# BEP31_RPM_BAR.net
KiCad netlist of a schematic drawn in EAGLE
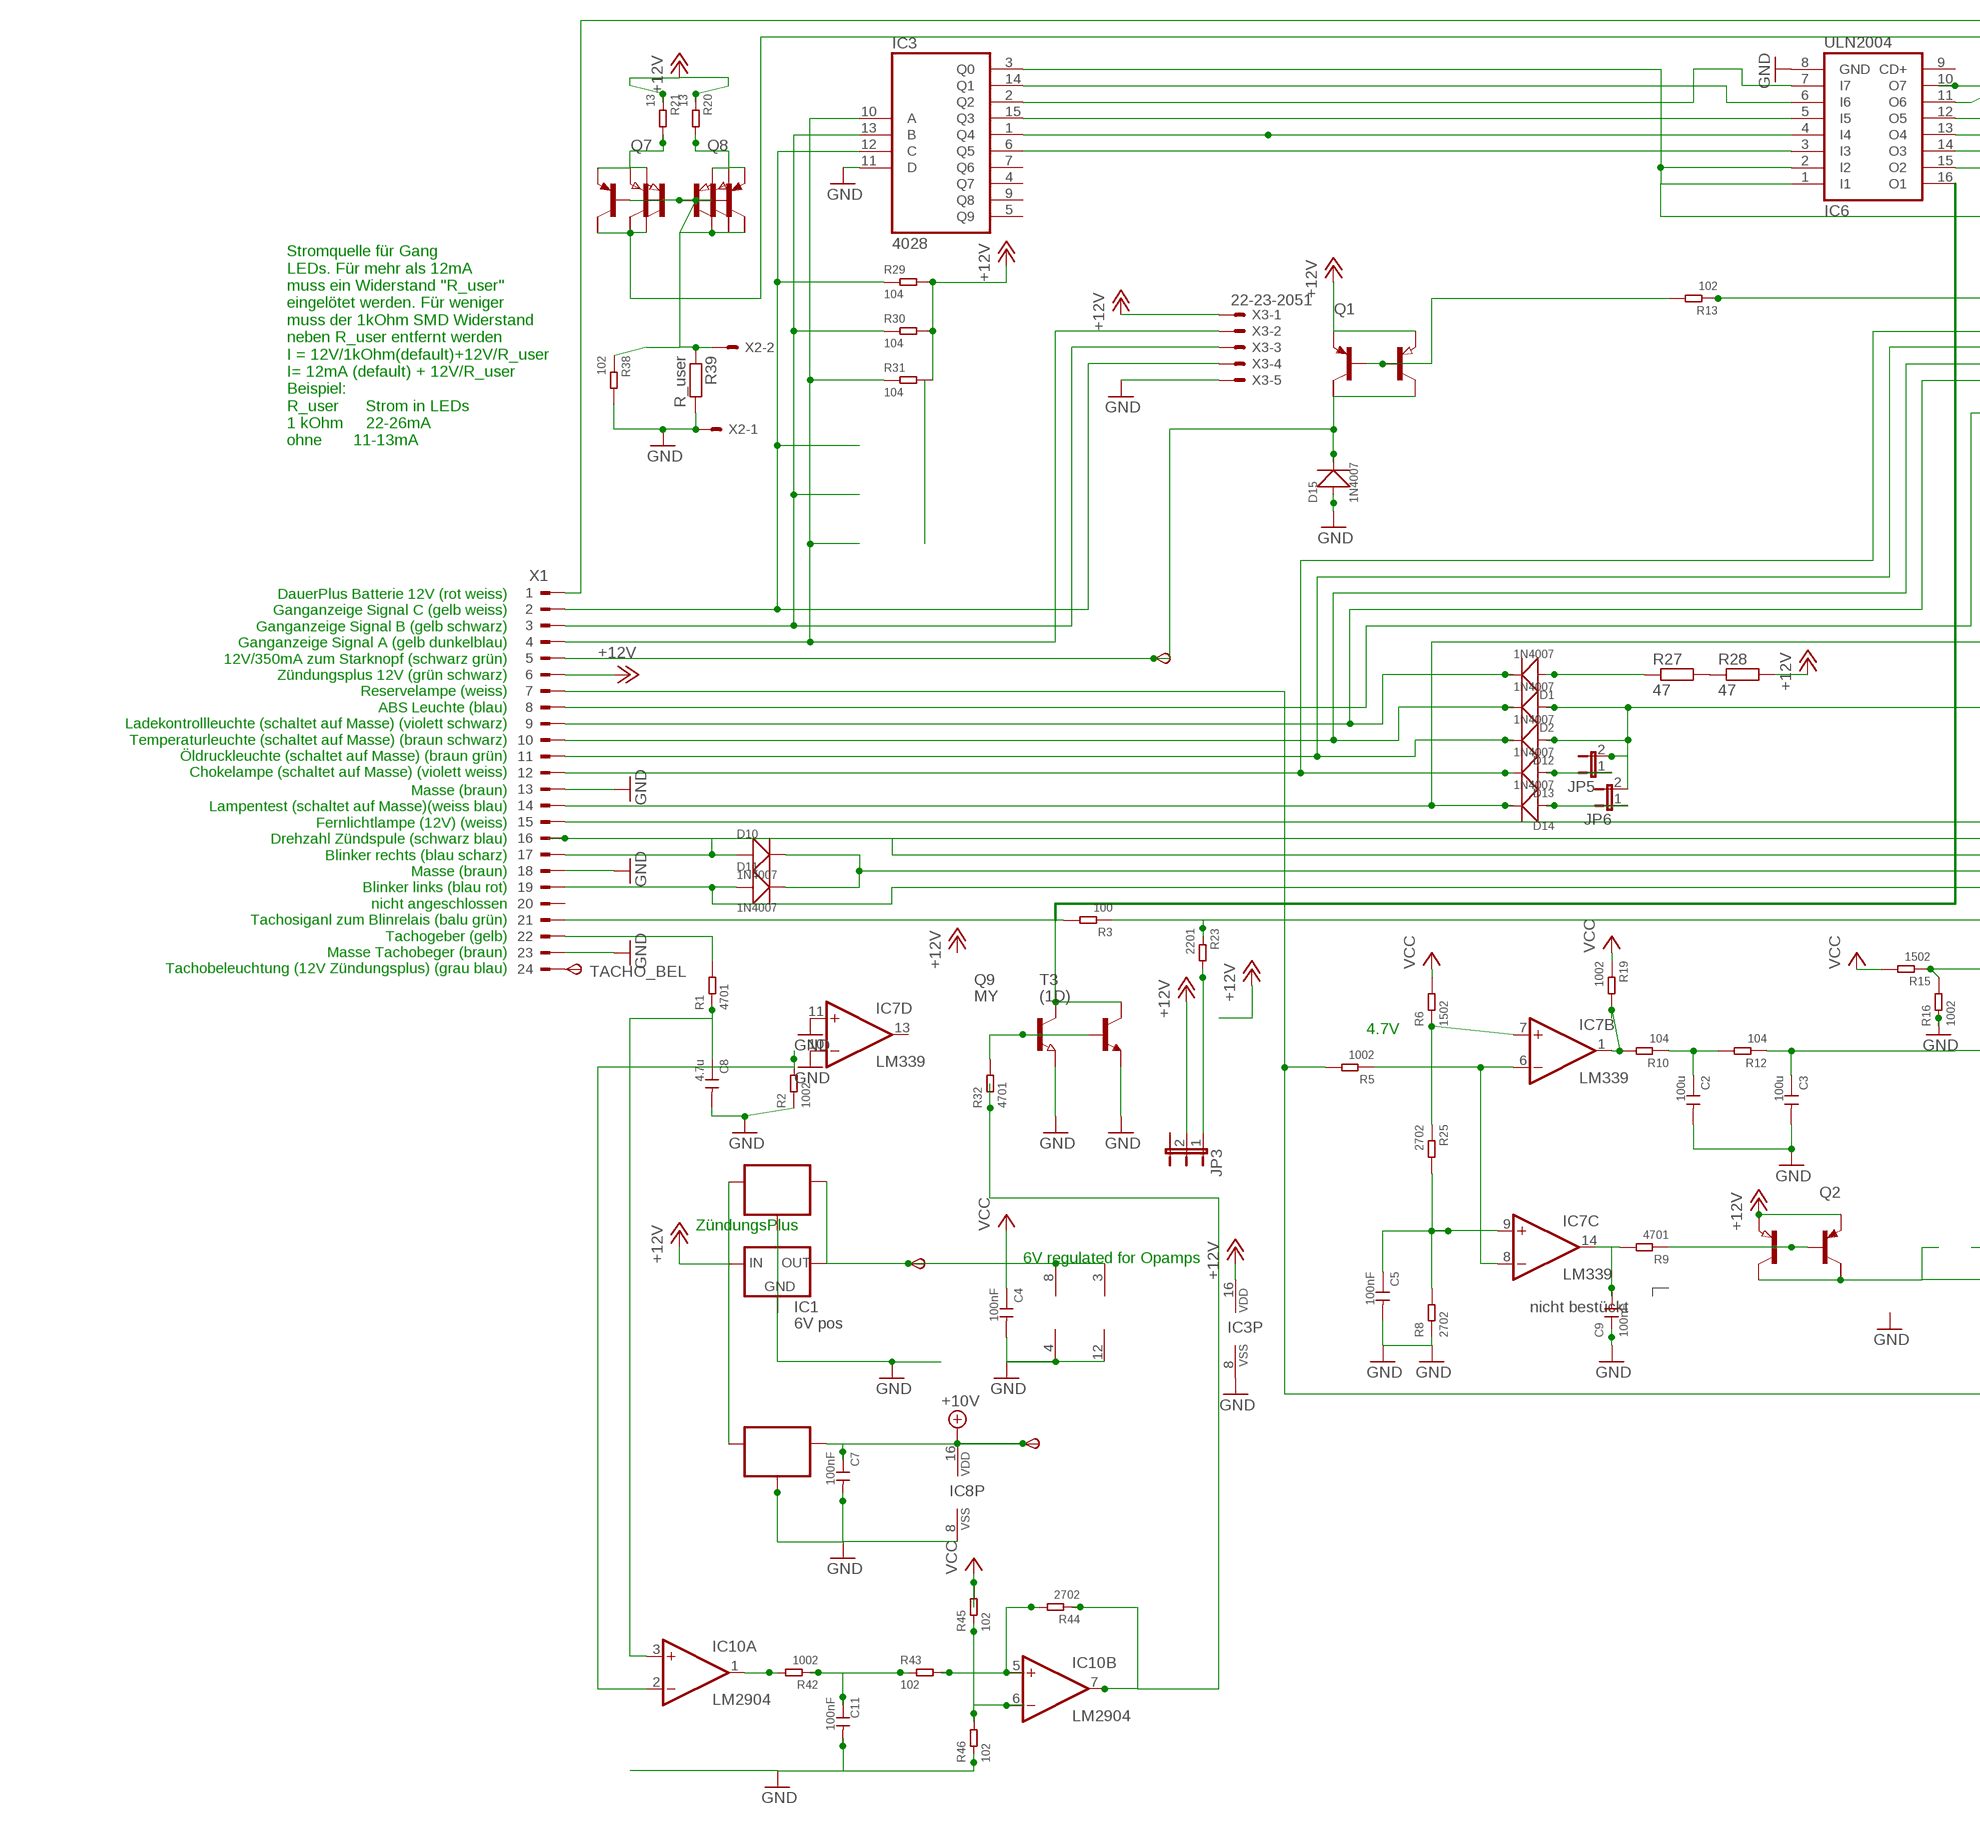
[diagram p0: schematic, sheet 1, part 1 of 2]
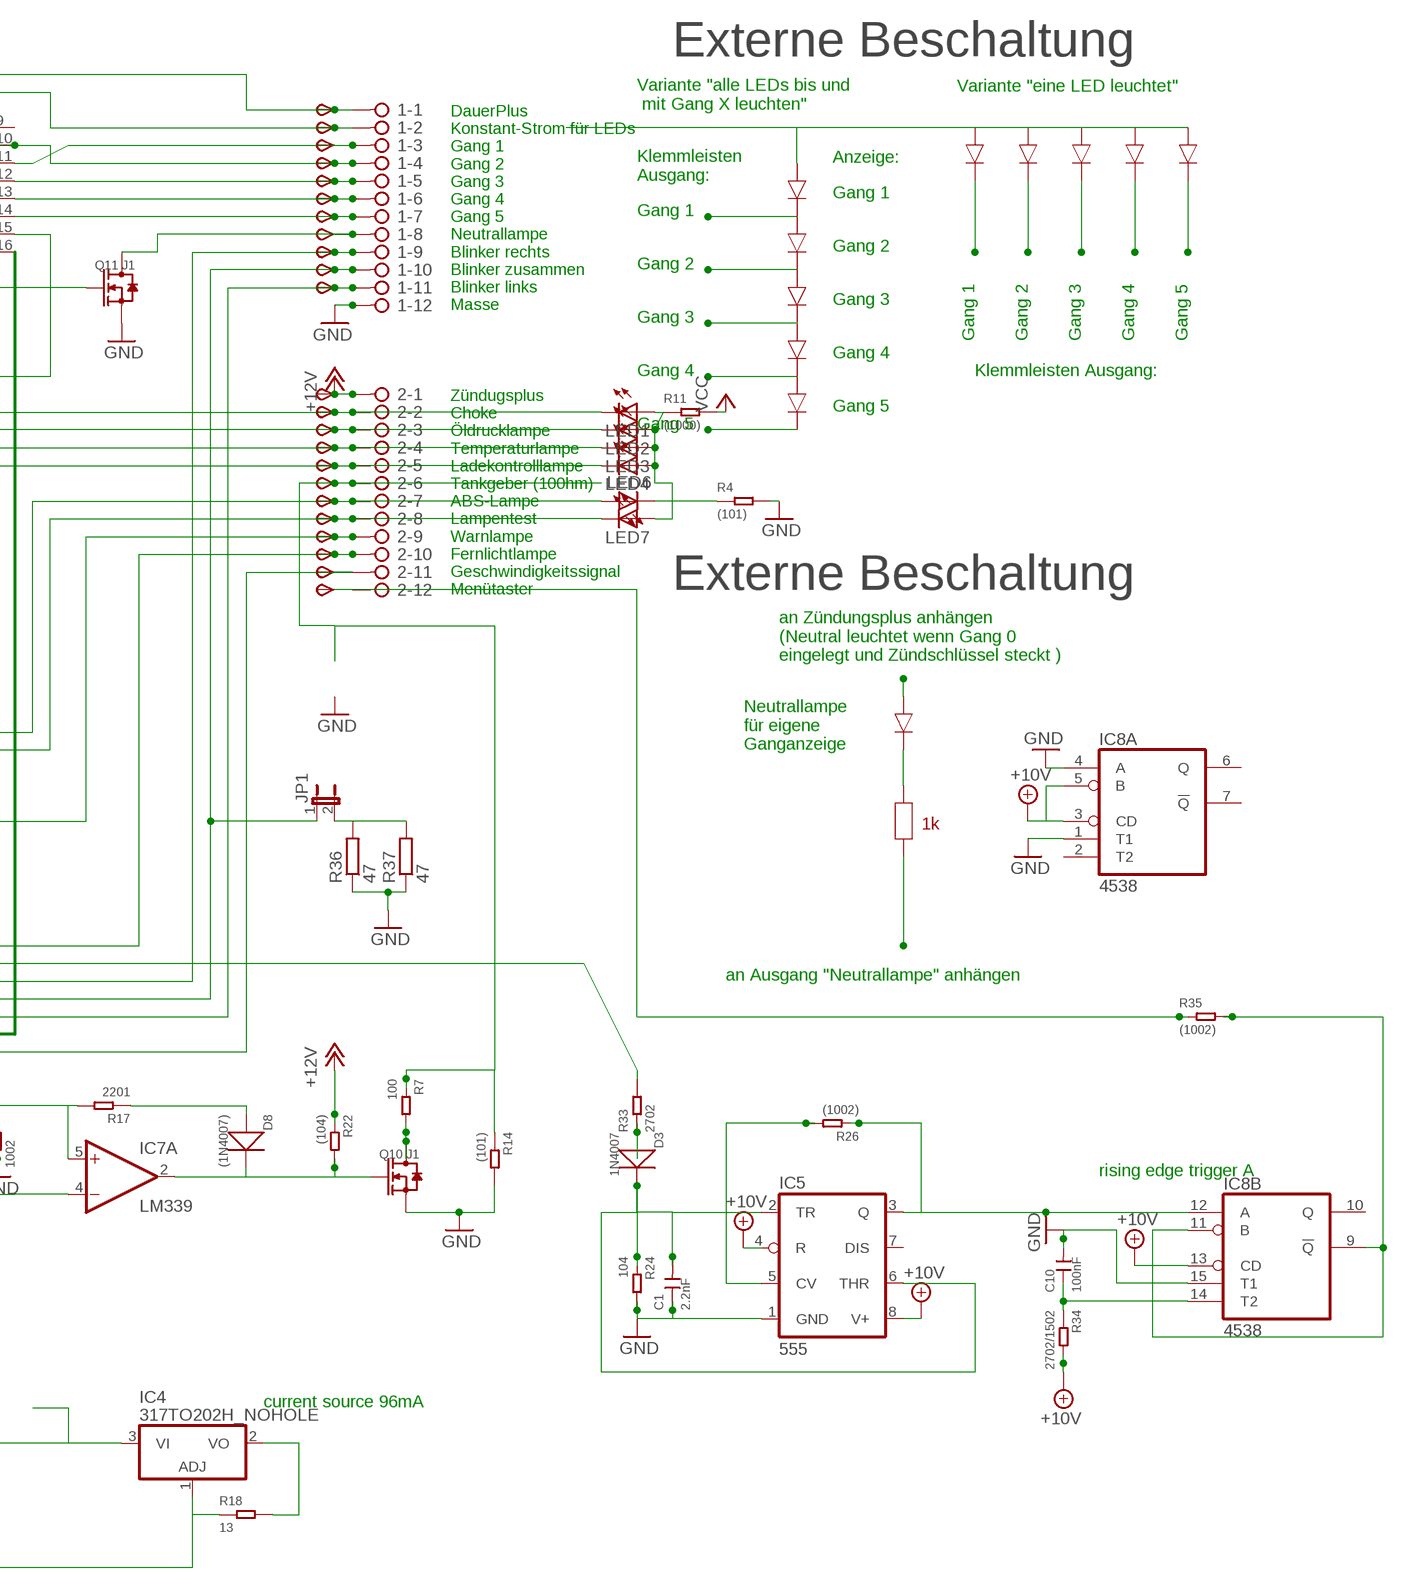
[diagram p1: schematic, sheet 1, part 2 of 2]

(export (version "E")
  (design (tool "Eeschema 10.0.6"))
  (components
    (comp (ref "1")
      (value "2081-1132")
      (footprint "eagle-import:12-PIN")
      (libsource (lib "eagle-import") (part "2081-1132"))
    )
    (comp (ref "2")
      (value "2081-1132")
      (footprint "eagle-import:12-PIN")
      (libsource (lib "eagle-import") (part "2081-1132"))
    )
    (comp (ref "6V")
      (value "TPSB1.8")
      (footprint "eagle-import:B1.8")
      (libsource (lib "eagle-import") (part "TPSB1.8"))
    )
    (comp (ref "10V")
      (value "TPSB1.8")
      (footprint "eagle-import:B1.8")
      (libsource (lib "eagle-import") (part "TPSB1.8"))
    )
    (comp (ref "C1")
      (value "2.2nF")
      (footprint "eagle-import:C0805")
      (fields (field (name "MPN") "CC0805KRX7R9BB104"))
      (libsource (lib "eagle-import") (part "CERAMIC-100NF-50V-10%-X7R(0805)"))
    )
    (comp (ref "C2")
      (value "100u")
      (footprint "eagle-import:C1206")
      (fields (field (name "MPN") "GRM31CR60J107ME39L"))
      (libsource (lib "eagle-import") (part "CERAMIC-100UF-6.3V-20%-X5R(1206)"))
    )
    (comp (ref "C3")
      (value "100u")
      (footprint "eagle-import:C1206")
      (fields (field (name "MPN") "GRM31CR60J107ME39L"))
      (libsource (lib "eagle-import") (part "CERAMIC-100UF-6.3V-20%-X5R(1206)"))
    )
    (comp (ref "C4")
      (value "100nF")
      (footprint "eagle-import:C0805")
      (fields (field (name "MPN") "CC0805KRX7R9BB104"))
      (libsource (lib "eagle-import") (part "CERAMIC-100NF-50V-10%-X7R(0805)"))
    )
    (comp (ref "C5")
      (value "100nF")
      (footprint "eagle-import:C0805")
      (fields (field (name "MPN") "CC0805KRX7R9BB104"))
      (libsource (lib "eagle-import") (part "CERAMIC-100NF-50V-10%-X7R(0805)"))
    )
    (comp (ref "C7")
      (value "100nF")
      (footprint "eagle-import:C0805")
      (fields (field (name "MPN") "CC0805KRX7R9BB104"))
      (libsource (lib "eagle-import") (part "CERAMIC-100NF-50V-10%-X7R(0805)"))
    )
    (comp (ref "C8")
      (value "4.7u")
      (footprint "eagle-import:C0805")
      (fields (field (name "MPN") "CC0805KKX5R8BB475"))
      (libsource (lib "eagle-import") (part "CERAMIC-4.7UF-25V-10%-X5R(0805)"))
    )
    (comp (ref "C9")
      (value "100nF")
      (footprint "eagle-import:C0805")
      (fields (field (name "MPN") "CC0805KRX7R9BB104"))
      (libsource (lib "eagle-import") (part "CERAMIC-100NF-50V-10%-X7R(0805)"))
    )
    (comp (ref "C10")
      (value "100nF")
      (footprint "eagle-import:C0805")
      (fields (field (name "MPN") "CC0805KRX7R9BB104"))
      (libsource (lib "eagle-import") (part "CERAMIC-100NF-50V-10%-X7R(0805)"))
    )
    (comp (ref "C11")
      (value "100nF")
      (footprint "eagle-import:C0805")
      (fields (field (name "MPN") "CC0805KRX7R9BB104"))
      (libsource (lib "eagle-import") (part "CERAMIC-100NF-50V-10%-X7R(0805)"))
    )
    (comp (ref "D1")
      (value "1N4007")
      (footprint "eagle-import:DO-214AC")
      (libsource (lib "eagle-import") (part "DIODE-GEN-PURPOSE-1KV-1A(DO-214AC)"))
    )
    (comp (ref "D2")
      (value "1N4007")
      (footprint "eagle-import:DO-214AC-1206MOUNT")
      (libsource (lib "eagle-import") (part "DIODE-GEN-PURPOSE-1KV-1A(DO-214AC)DO-214AC/1206"))
    )
    (comp (ref "D3")
      (value "1N4007")
      (footprint "eagle-import:DO-214AC")
      (libsource (lib "eagle-import") (part "DIODE-GEN-PURPOSE-1KV-1A(DO-214AC)"))
    )
    (comp (ref "D8")
      (value "(1N4007)")
      (footprint "eagle-import:DO-214AC-1206MOUNT")
      (libsource (lib "eagle-import") (part "DIODE-GEN-PURPOSE-1KV-1A(DO-214AC)DO-214AC/1206"))
    )
    (comp (ref "D10")
      (value "1N4007")
      (footprint "eagle-import:DO-214AC")
      (libsource (lib "eagle-import") (part "DIODE-GEN-PURPOSE-1KV-1A(DO-214AC)"))
    )
    (comp (ref "D11")
      (value "1N4007")
      (footprint "eagle-import:DO-214AC")
      (libsource (lib "eagle-import") (part "DIODE-GEN-PURPOSE-1KV-1A(DO-214AC)"))
    )
    (comp (ref "D12")
      (value "1N4007")
      (footprint "eagle-import:DO-214AC-1206MOUNT")
      (libsource (lib "eagle-import") (part "DIODE-GEN-PURPOSE-1KV-1A(DO-214AC)DO-214AC/1206"))
    )
    (comp (ref "D13")
      (value "1N4007")
      (footprint "eagle-import:DO-214AC-1206MOUNT")
      (libsource (lib "eagle-import") (part "DIODE-GEN-PURPOSE-1KV-1A(DO-214AC)DO-214AC/1206"))
    )
    (comp (ref "D14")
      (value "1N4007")
      (footprint "eagle-import:DO-214AC-1206MOUNT")
      (libsource (lib "eagle-import") (part "DIODE-GEN-PURPOSE-1KV-1A(DO-214AC)DO-214AC/1206"))
    )
    (comp (ref "D15")
      (value "1N4007")
      (footprint "eagle-import:DO-214AC")
      (libsource (lib "eagle-import") (part "DIODE-GEN-PURPOSE-1KV-1A(DO-214AC)"))
    )
    (comp (ref "IC1")
      (value "6V pos")
      (footprint "eagle-import:78LXX")
      (libsource (lib "eagle-import") (part "v-reg_78LXX"))
    )
    (comp (ref "IC2")
      (value "78LXXSOT89_ROUND")
      (footprint "eagle-import:SOT89_ROUND")
      (libsource (lib "eagle-import") (part "78LXXSOT89_ROUND"))
    )
    (comp (ref "IC3")
      (value "4028")
      (footprint "eagle-import:SO16")
      (libsource (lib "eagle-import") (part "4028D"))
    )
    (comp (ref "IC4")
      (value "317TO202H_NOHOLE")
      (footprint "eagle-import:TO220H_NOHOLE")
      (libsource (lib "eagle-import") (part "317TO202H_NOHOLE"))
    )
    (comp (ref "IC5")
      (value "555")
      (footprint "eagle-import:SO08")
      (libsource (lib "eagle-import") (part "555DNE"))
    )
    (comp (ref "IC6")
      (value "ULN2004")
      (footprint "eagle-import:SO16")
      (libsource (lib "eagle-import") (part "ULN2004AD"))
    )
    (comp (ref "IC7")
      (value "LM339")
      (footprint "eagle-import:SO14")
      (libsource (lib "eagle-import") (part "LM339D"))
    )
    (comp (ref "IC8")
      (value "4538")
      (footprint "eagle-import:SO16")
      (libsource (lib "eagle-import") (part "4538D"))
    )
    (comp (ref "IC9")
      (value "78LXXSOT89_ROUND")
      (footprint "eagle-import:SOT89_ROUND")
      (libsource (lib "eagle-import") (part "78LXXSOT89_ROUND"))
    )
    (comp (ref "IC10")
      (value "LM2904")
      (footprint "eagle-import:SO08")
      (libsource (lib "eagle-import") (part "LM358D"))
    )
    (comp (ref "JP1")
      (value "JP1E")
      (footprint "eagle-import:JP1")
      (libsource (lib "eagle-import") (part "JP1E"))
    )
    (comp (ref "JP3")
      (value "JP2E")
      (footprint "eagle-import:JP2")
      (libsource (lib "eagle-import") (part "JP2E"))
    )
    (comp (ref "JP5")
      (value "JP1E")
      (footprint "eagle-import:JP1")
      (libsource (lib "eagle-import") (part "JP1E"))
    )
    (comp (ref "JP6")
      (value "JP1E")
      (footprint "eagle-import:JP1")
      (libsource (lib "eagle-import") (part "JP1E"))
    )
    (comp (ref "LED1")
      (value "LEDLD260")
      (footprint "eagle-import:LD260")
      (libsource (lib "eagle-import") (part "LEDLD260"))
    )
    (comp (ref "LED2")
      (value "LEDLD260")
      (footprint "eagle-import:LD260")
      (libsource (lib "eagle-import") (part "LEDLD260"))
    )
    (comp (ref "LED3")
      (value "LEDLD260")
      (footprint "eagle-import:LD260")
      (libsource (lib "eagle-import") (part "LEDLD260"))
    )
    (comp (ref "LED4")
      (value "LEDLD260")
      (footprint "eagle-import:LD260")
      (libsource (lib "eagle-import") (part "LEDLD260"))
    )
    (comp (ref "LED6")
      (value "LEDLD260")
      (footprint "eagle-import:LD260")
      (libsource (lib "eagle-import") (part "LEDLD260"))
    )
    (comp (ref "LED7")
      (value "LEDLD260")
      (footprint "eagle-import:LD260")
      (libsource (lib "eagle-import") (part "LEDLD260"))
    )
    (comp (ref "Q1")
      (value "PNP-TRANSISTOR_SOT89")
      (footprint "eagle-import:SOT89")
      (libsource (lib "eagle-import") (part "PNP-TRANSISTOR_SOT89"))
    )
    (comp (ref "Q2")
      (value "PNP-TRANSISTOR_SOT89")
      (footprint "eagle-import:SOT89")
      (libsource (lib "eagle-import") (part "PNP-TRANSISTOR_SOT89"))
    )
    (comp (ref "Q3")
      (value "AH-16")
      (footprint "eagle-import:SOT223")
      (libsource (lib "eagle-import") (part "BCP53T1"))
    )
    (comp (ref "Q4")
      (value "(AH-16)")
      (footprint "eagle-import:SOT223")
      (libsource (lib "eagle-import") (part "BCP53T1"))
    )
    (comp (ref "Q5")
      (value "(AH-16)")
      (footprint "eagle-import:SOT223")
      (libsource (lib "eagle-import") (part "BCP53T1"))
    )
    (comp (ref "Q6")
      (value "(AH-16)")
      (footprint "eagle-import:SOT223")
      (libsource (lib "eagle-import") (part "BCP53T1"))
    )
    (comp (ref "Q7")
      (value "PNP-TRANSISTOR_SOT89")
      (footprint "eagle-import:SOT89")
      (libsource (lib "eagle-import") (part "PNP-TRANSISTOR_SOT89"))
    )
    (comp (ref "Q8")
      (value "PNP-TRANSISTOR_SOT89")
      (footprint "eagle-import:SOT89")
      (libsource (lib "eagle-import") (part "PNP-TRANSISTOR_SOT89"))
    )
    (comp (ref "Q9")
      (value "MY")
      (footprint "eagle-import:SOT89")
      (libsource (lib "eagle-import") (part "NPN-TRANSISTOR_SOT89"))
    )
    (comp (ref "Q10")
      (value "J1")
      (footprint "eagle-import:SOT-23")
      (fields (field (name "MPN") "BSS138W-7-F"))
      (libsource (lib "eagle-import") (part "SMD-MOSFET-N-CH-50V-200MA-BSS138W-7-F(SOT-23)"))
    )
    (comp (ref "Q11")
      (value "J1")
      (footprint "eagle-import:SOT-23")
      (fields (field (name "MPN") "BSS138W-7-F"))
      (libsource (lib "eagle-import") (part "SMD-MOSFET-N-CH-50V-200MA-BSS138W-7-F(SOT-23)"))
    )
    (comp (ref "R1")
      (value "4701")
      (footprint "eagle-import:R0805")
      (fields (field (name "MPN") "RC0805JR-074K7L"))
      (libsource (lib "eagle-import") (part "SMD-RES-4.7K-5%-1/8W(0805)"))
    )
    (comp (ref "R2")
      (value "1002")
      (footprint "eagle-import:R0805")
      (fields (field (name "MPN") "RC0805FR-0710KL"))
      (libsource (lib "eagle-import") (part "SMD-RES-10K-1%-1/8W(0805)"))
    )
    (comp (ref "R3")
      (value "100")
      (footprint "eagle-import:R0805")
      (fields (field (name "MPN") "RC0805JR-07220RL"))
      (libsource (lib "eagle-import") (part "SMD-RES-220R-5%-1/8W(0805)"))
    )
    (comp (ref "R4")
      (value "(101)")
      (footprint "eagle-import:R0805")
      (fields (field (name "MPN") "RC0805JR-07100RL"))
      (libsource (lib "eagle-import") (part "SMD-RES-100R-5%-1/8W(0805)"))
    )
    (comp (ref "R5")
      (value "1002")
      (footprint "eagle-import:R0805")
      (fields (field (name "MPN") "RC0805FR-0710KL"))
      (libsource (lib "eagle-import") (part "SMD-RES-10K-1%-1/8W(0805)"))
    )
    (comp (ref "R6")
      (value "1502")
      (footprint "eagle-import:R0805")
      (fields (field (name "MPN") "RC0805FR-0710KL"))
      (libsource (lib "eagle-import") (part "SMD-RES-10K-1%-1/8W(0805)"))
    )
    (comp (ref "R7")
      (value "100")
      (footprint "eagle-import:R0805")
      (fields (field (name "MPN") "RC0805JR-072K2L"))
      (libsource (lib "eagle-import") (part "SMD-RES-2.2K-5%-1/8W(0805)"))
    )
    (comp (ref "R8")
      (value "2702")
      (footprint "eagle-import:R0805")
      (fields (field (name "MPN") "RC0805JR-074K7L"))
      (libsource (lib "eagle-import") (part "SMD-RES-4.7K-5%-1/8W(0805)"))
    )
    (comp (ref "R9")
      (value "4701")
      (footprint "eagle-import:R0805")
      (fields (field (name "MPN") "RC0805JR-074K7L"))
      (libsource (lib "eagle-import") (part "SMD-RES-4.7K-5%-1/8W(0805)"))
    )
    (comp (ref "R10")
      (value "104")
      (footprint "eagle-import:R0805")
      (fields (field (name "MPN") "RC0805FR-0710KL"))
      (libsource (lib "eagle-import") (part "SMD-RES-10K-1%-1/8W(0805)"))
    )
    (comp (ref "R11")
      (value "(1000)")
      (footprint "eagle-import:R0805")
      (fields (field (name "MPN") "RC0805JR-07100RL"))
      (libsource (lib "eagle-import") (part "SMD-RES-100R-5%-1/8W(0805)"))
    )
    (comp (ref "R12")
      (value "104")
      (footprint "eagle-import:R0805")
      (fields (field (name "MPN") "RC0805FR-0710KL"))
      (libsource (lib "eagle-import") (part "SMD-RES-10K-1%-1/8W(0805)"))
    )
    (comp (ref "R13")
      (value "102")
      (footprint "eagle-import:R0805")
      (fields (field (name "MPN") "RC0805JR-071KL"))
      (libsource (lib "eagle-import") (part "SMD-RES-1K-5%-1/8W(0805)"))
    )
    (comp (ref "R14")
      (value "(101)")
      (footprint "eagle-import:R0805")
      (fields (field (name "MPN") "RC0805JR-072K2L"))
      (libsource (lib "eagle-import") (part "SMD-RES-2.2K-5%-1/8W(0805)"))
    )
    (comp (ref "R15")
      (value "1502")
      (footprint "eagle-import:R0805")
      (fields (field (name "MPN") "RC0805FR-0710KL"))
      (libsource (lib "eagle-import") (part "SMD-RES-10K-1%-1/8W(0805)"))
    )
    (comp (ref "R16")
      (value "1002")
      (footprint "eagle-import:R0805")
      (fields (field (name "MPN") "RC0805FR-0710KL"))
      (libsource (lib "eagle-import") (part "SMD-RES-10K-1%-1/8W(0805)"))
    )
    (comp (ref "R17")
      (value "2201")
      (footprint "eagle-import:R0805")
      (fields (field (name "MPN") "RC0805JR-072K2L"))
      (libsource (lib "eagle-import") (part "SMD-RES-2.2K-5%-1/8W(0805)"))
    )
    (comp (ref "R18")
      (value "13")
      (footprint "eagle-import:R1206")
      (fields (field (name "MPN") "RC1206JR-0713RL"))
      (libsource (lib "eagle-import") (part "SMD-RES-13R-5%-1/4W(1206)"))
    )
    (comp (ref "R19")
      (value "1002")
      (footprint "eagle-import:R0805")
      (fields (field (name "MPN") "RC0805FR-0710KL"))
      (libsource (lib "eagle-import") (part "SMD-RES-10K-1%-1/8W(0805)"))
    )
    (comp (ref "R20")
      (value "13")
      (footprint "eagle-import:R1206")
      (fields (field (name "MPN") "RC1206JR-0713RL"))
      (libsource (lib "eagle-import") (part "SMD-RES-13R-5%-1/4W(1206)"))
    )
    (comp (ref "R21")
      (value "13")
      (footprint "eagle-import:R1206")
      (fields (field (name "MPN") "RC1206JR-0713RL"))
      (libsource (lib "eagle-import") (part "SMD-RES-13R-5%-1/4W(1206)"))
    )
    (comp (ref "R22")
      (value "(104)")
      (footprint "eagle-import:R0805")
      (fields (field (name "MPN") "RC0805FR-0710KL"))
      (libsource (lib "eagle-import") (part "SMD-RES-10K-1%-1/8W(0805)"))
    )
    (comp (ref "R23")
      (value "2201")
      (footprint "eagle-import:R0805")
      (fields (field (name "MPN") "RC0805JR-072K2L"))
      (libsource (lib "eagle-import") (part "SMD-RES-2.2K-5%-1/8W(0805)"))
    )
    (comp (ref "R24")
      (value "104")
      (footprint "eagle-import:R0805")
      (fields (field (name "MPN") "RC0805FR-0710KL"))
      (libsource (lib "eagle-import") (part "SMD-RES-10K-1%-1/8W(0805)"))
    )
    (comp (ref "R25")
      (value "2702")
      (footprint "eagle-import:R0805")
      (fields (field (name "MPN") "RC0805JR-074K7L"))
      (libsource (lib "eagle-import") (part "SMD-RES-4.7K-5%-1/8W(0805)"))
    )
    (comp (ref "R26")
      (value "(1002)")
      (footprint "eagle-import:R0805")
      (fields (field (name "MPN") "RC0805FR-0710KL"))
      (libsource (lib "eagle-import") (part "SMD-RES-10K-1%-1/8W(0805)"))
    )
    (comp (ref "R27")
      (value "47")
      (footprint "eagle-import:V235_17_1MM")
      (libsource (lib "eagle-import") (part "R-EU_V235/17_1MM"))
    )
    (comp (ref "R28")
      (value "47")
      (footprint "eagle-import:V235_17_1MM")
      (libsource (lib "eagle-import") (part "R-EU_V235/17_1MM"))
    )
    (comp (ref "R29")
      (value "104")
      (footprint "eagle-import:R0805")
      (fields (field (name "MPN") "RC0805FR-0710KL"))
      (libsource (lib "eagle-import") (part "SMD-RES-10K-1%-1/8W(0805)"))
    )
    (comp (ref "R30")
      (value "104")
      (footprint "eagle-import:R0805")
      (fields (field (name "MPN") "RC0805FR-0710KL"))
      (libsource (lib "eagle-import") (part "SMD-RES-10K-1%-1/8W(0805)"))
    )
    (comp (ref "R31")
      (value "104")
      (footprint "eagle-import:R0805")
      (fields (field (name "MPN") "RC0805FR-0710KL"))
      (libsource (lib "eagle-import") (part "SMD-RES-10K-1%-1/8W(0805)"))
    )
    (comp (ref "R32")
      (value "4701")
      (footprint "eagle-import:R0805")
      (fields (field (name "MPN") "RC0805JR-074K7L"))
      (libsource (lib "eagle-import") (part "SMD-RES-4.7K-5%-1/8W(0805)"))
    )
    (comp (ref "R33")
      (value "2702")
      (footprint "eagle-import:R0805")
      (fields (field (name "MPN") "RC0805FR-0710KL"))
      (libsource (lib "eagle-import") (part "SMD-RES-10K-1%-1/8W(0805)"))
    )
    (comp (ref "R34")
      (value "2702/1502")
      (footprint "eagle-import:R0805")
      (fields (field (name "MPN") "RC0805JR-074K7L"))
      (libsource (lib "eagle-import") (part "SMD-RES-4.7K-5%-1/8W(0805)"))
    )
    (comp (ref "R35")
      (value "(1002)")
      (footprint "eagle-import:R0805")
      (fields (field (name "MPN") "RC0805JR-074K7L"))
      (libsource (lib "eagle-import") (part "SMD-RES-4.7K-5%-1/8W(0805)"))
    )
    (comp (ref "R36")
      (value "47")
      (footprint "eagle-import:V235_17_1MM")
      (libsource (lib "eagle-import") (part "R-EU_V235/17_1MM"))
    )
    (comp (ref "R37")
      (value "47")
      (footprint "eagle-import:V235_17_1MM")
      (libsource (lib "eagle-import") (part "R-EU_V235/17_1MM"))
    )
    (comp (ref "R38")
      (value "102")
      (footprint "eagle-import:R0805")
      (fields (field (name "MPN") "RC0805JR-071KL"))
      (libsource (lib "eagle-import") (part "SMD-RES-1K-5%-1/8W(0805)"))
    )
    (comp (ref "R39")
      (value "R_user")
      (footprint "eagle-import:R0805")
      (libsource (lib "eagle-import") (part "R-EU_R0805"))
    )
    (comp (ref "R42")
      (value "1002")
      (footprint "eagle-import:R0805")
      (fields (field (name "MPN") "RC0805FR-0710KL"))
      (libsource (lib "eagle-import") (part "SMD-RES-10K-1%-1/8W(0805)"))
    )
    (comp (ref "R43")
      (value "102")
      (footprint "eagle-import:R0805")
      (fields (field (name "MPN") "RC0805JR-071KL"))
      (libsource (lib "eagle-import") (part "SMD-RES-1K-5%-1/8W(0805)"))
    )
    (comp (ref "R44")
      (value "2702")
      (footprint "eagle-import:R0805")
      (fields (field (name "MPN") "RC0805JR-074K7L"))
      (libsource (lib "eagle-import") (part "SMD-RES-4.7K-5%-1/8W(0805)"))
    )
    (comp (ref "R45")
      (value "102")
      (footprint "eagle-import:R0805")
      (fields (field (name "MPN") "RC0805JR-071KL"))
      (libsource (lib "eagle-import") (part "SMD-RES-1K-5%-1/8W(0805)"))
    )
    (comp (ref "R46")
      (value "102")
      (footprint "eagle-import:R0805")
      (fields (field (name "MPN") "RC0805JR-071KL"))
      (libsource (lib "eagle-import") (part "SMD-RES-1K-5%-1/8W(0805)"))
    )
    (comp (ref "START")
      (value "TPSB1.8")
      (footprint "eagle-import:B1.8")
      (libsource (lib "eagle-import") (part "TPSB1.8"))
    )
    (comp (ref "T1")
      (value "PNP2SM8")
      (footprint "eagle-import:SM8")
      (libsource (lib "eagle-import") (part "PNP2SM8"))
    )
    (comp (ref "T3")
      (value "(1D)")
      (footprint "eagle-import:SOT23-BEC")
      (libsource (lib "eagle-import") (part "-NPN-SOT23-BECMMBTA42LT1"))
    )
    (comp (ref "TACHO_BEL")
      (value "TPSP1_1MM")
      (footprint "eagle-import:P1_1.0MM")
      (libsource (lib "eagle-import") (part "TPSP1_1MM"))
    )
    (comp (ref "TP1")
      (value "TPSB1.8")
      (footprint "eagle-import:B1.8")
      (libsource (lib "eagle-import") (part "TPSB1.8"))
    )
    (comp (ref "TP2")
      (value "TPSB1.8")
      (footprint "eagle-import:B1.8")
      (libsource (lib "eagle-import") (part "TPSB1.8"))
    )
    (comp (ref "TP3")
      (value "TPSB1.8")
      (footprint "eagle-import:B1.8")
      (libsource (lib "eagle-import") (part "TPSB1.8"))
    )
    (comp (ref "TP4")
      (value "TPSB1.8")
      (footprint "eagle-import:B1.8")
      (libsource (lib "eagle-import") (part "TPSB1.8"))
    )
    (comp (ref "TP5")
      (value "TPSB1.8")
      (footprint "eagle-import:B1.8")
      (libsource (lib "eagle-import") (part "TPSB1.8"))
    )
    (comp (ref "TP6")
      (value "TPSB1.8")
      (footprint "eagle-import:B1.8")
      (libsource (lib "eagle-import") (part "TPSB1.8"))
    )
    (comp (ref "TP7")
      (value "TPSB1.8")
      (footprint "eagle-import:B1.8")
      (libsource (lib "eagle-import") (part "TPSB1.8"))
    )
    (comp (ref "TP8")
      (value "TPSB1.8")
      (footprint "eagle-import:B1.8")
      (libsource (lib "eagle-import") (part "TPSB1.8"))
    )
    (comp (ref "TP9")
      (value "TPSB1.8")
      (footprint "eagle-import:B1.8")
      (libsource (lib "eagle-import") (part "TPSB1.8"))
    )
    (comp (ref "TP10")
      (value "TPSB1.8")
      (footprint "eagle-import:B1.8")
      (libsource (lib "eagle-import") (part "TPSB1.8"))
    )
    (comp (ref "TP11")
      (value "TPSB1.8")
      (footprint "eagle-import:B1.8")
      (libsource (lib "eagle-import") (part "TPSB1.8"))
    )
    (comp (ref "TP12")
      (value "TPSB1.8")
      (footprint "eagle-import:B1.8")
      (libsource (lib "eagle-import") (part "TPSB1.8"))
    )
    (comp (ref "TP13")
      (value "TPSB1,27")
      (footprint "eagle-import:B1,27")
      (libsource (lib "eagle-import") (part "TPSB1,27"))
    )
    (comp (ref "TP16")
      (value "TPSB1.8")
      (footprint "eagle-import:B1.8")
      (libsource (lib "eagle-import") (part "TPSB1.8"))
    )
    (comp (ref "TP17")
      (value "TPSB1.8")
      (footprint "eagle-import:B1.8")
      (libsource (lib "eagle-import") (part "TPSB1.8"))
    )
    (comp (ref "TP18")
      (value "TPSB1.8")
      (footprint "eagle-import:B1.8")
      (libsource (lib "eagle-import") (part "TPSB1.8"))
    )
    (comp (ref "TP19")
      (value "TPSB1.8")
      (footprint "eagle-import:B1.8")
      (libsource (lib "eagle-import") (part "TPSB1.8"))
    )
    (comp (ref "TP21")
      (value "TPSB1.8")
      (footprint "eagle-import:B1.8")
      (libsource (lib "eagle-import") (part "TPSB1.8"))
    )
    (comp (ref "TP22")
      (value "TPSB1.8")
      (footprint "eagle-import:B1.8")
      (libsource (lib "eagle-import") (part "TPSB1.8"))
    )
    (comp (ref "TP23")
      (value "TPSB1.8")
      (footprint "eagle-import:B1.8")
      (libsource (lib "eagle-import") (part "TPSB1.8"))
    )
    (comp (ref "TP24")
      (value "TPSB1,27")
      (footprint "eagle-import:B1,27")
      (libsource (lib "eagle-import") (part "TPSB1,27"))
    )
    (comp (ref "TP25")
      (value "TPSB1.8")
      (footprint "eagle-import:B1.8")
      (libsource (lib "eagle-import") (part "TPSB1.8"))
    )
    (comp (ref "TP26")
      (value "TPSB1.8")
      (footprint "eagle-import:B1.8")
      (libsource (lib "eagle-import") (part "TPSB1.8"))
    )
    (comp (ref "X1")
      (value "CON_BMWV2")
      (footprint "eagle-import:24-PIN_V2")
      (libsource (lib "eagle-import") (part "CON_BMWV2"))
    )
    (comp (ref "X2")
      (value "22-23-2021")
      (footprint "eagle-import:22-23-2021")
      (fields (field (name "MF") "MOLEX"))
      (libsource (lib "eagle-import") (part "22-23-2021"))
    )
    (comp (ref "X3")
      (value "22-23-2051")
      (footprint "eagle-import:22-23-2051")
      (fields (field (name "MF") "MOLEX"))
      (libsource (lib "eagle-import") (part "22-23-2051"))
    )
  )
  (nets
    (net (code "1") (name "+10V") (class "Default")
      (node (ref "10V") (pin "TP") (pinfunction "PP_TP") (pintype "input"))
      (node (ref "C7") (pin "1") (pinfunction "1_1") (pintype "passive"))
      (node (ref "IC5") (pin "4") (pinfunction "R_4") (pintype "input"))
      (node (ref "IC5") (pin "8") (pinfunction "V+_8") (pintype "power_in"))
      (node (ref "IC8") (pin "13") (pinfunction "CD_13") (pintype "input"))
      (node (ref "IC8") (pin "16") (pinfunction "VDD_16") (pintype "power_in"))
      (node (ref "IC8") (pin "3") (pinfunction "CD_3") (pintype "input"))
      (node (ref "IC8") (pin "5") (pinfunction "B_5") (pintype "input"))
      (node (ref "IC9") (pin "1") (pinfunction "OUT_1") (pintype "passive"))
      (node (ref "R34") (pin "2") (pinfunction "2_2") (pintype "passive"))
    )
    (net (code "2") (name "+12V") (class "Default")
      (node (ref "2") (pin "1") (pinfunction "KL_1") (pintype "passive"))
      (node (ref "IC1") (pin "IN") (pinfunction "IN_IN") (pintype "input"))
      (node (ref "IC2") (pin "3") (pinfunction "IN_3") (pintype "input"))
      (node (ref "IC3") (pin "16") (pinfunction "VDD_16") (pintype "power_in"))
      (node (ref "IC9") (pin "3") (pinfunction "IN_3") (pintype "input"))
      (node (ref "JP3") (pin "2") (pinfunction "2_2") (pintype "passive"))
      (node (ref "Q1") (pin "3") (pinfunction "E_3") (pintype "passive"))
      (node (ref "Q2") (pin "3") (pinfunction "E_3") (pintype "passive"))
      (node (ref "Q3") (pin "3") (pinfunction "E_3") (pintype "passive"))
      (node (ref "Q4") (pin "3") (pinfunction "E_3") (pintype "passive"))
      (node (ref "R20") (pin "1") (pinfunction "1_1") (pintype "passive"))
      (node (ref "R21") (pin "1") (pinfunction "1_1") (pintype "passive"))
      (node (ref "R22") (pin "1") (pinfunction "1_1") (pintype "passive"))
      (node (ref "R28") (pin "2") (pinfunction "2_2") (pintype "passive"))
      (node (ref "R29") (pin "2") (pinfunction "2_2") (pintype "passive"))
      (node (ref "R30") (pin "2") (pinfunction "2_2") (pintype "passive"))
      (node (ref "R31") (pin "2") (pinfunction "2_2") (pintype "passive"))
      (node (ref "TP12") (pin "TP") (pinfunction "PP_TP") (pintype "input"))
      (node (ref "X1") (pin "6") (pinfunction "6_6") (pintype "passive"))
      (node (ref "X3") (pin "1") (pinfunction "S_1") (pintype "passive"))
    )
    (net (code "3") (name "GND") (class "Default")
      (node (ref "1") (pin "12") (pinfunction "KL_12") (pintype "passive"))
      (node (ref "C1") (pin "1") (pinfunction "1_1") (pintype "passive"))
      (node (ref "C10") (pin "2") (pinfunction "2_2") (pintype "passive"))
      (node (ref "C11") (pin "2") (pinfunction "2_2") (pintype "passive"))
      (node (ref "C2") (pin "2") (pinfunction "2_2") (pintype "passive"))
      (node (ref "C3") (pin "2") (pinfunction "2_2") (pintype "passive"))
      (node (ref "C4") (pin "2") (pinfunction "2_2") (pintype "passive"))
      (node (ref "C5") (pin "2") (pinfunction "2_2") (pintype "passive"))
      (node (ref "C7") (pin "2") (pinfunction "2_2") (pintype "passive"))
      (node (ref "C8") (pin "2") (pinfunction "2_2") (pintype "passive"))
      (node (ref "C9") (pin "1") (pinfunction "1_1") (pintype "passive"))
      (node (ref "D15") (pin "1") (pinfunction "+_1") (pintype "passive"))
      (node (ref "IC1") (pin "GND") (pinfunction "GND_GND") (pintype "input"))
      (node (ref "IC10") (pin "4") (pinfunction "V-_4") (pintype "power_in"))
      (node (ref "IC2") (pin "2") (pinfunction "GND_2") (pintype "input"))
      (node (ref "IC2") (pin "2@1") (pinfunction "GND_2@1") (pintype "input"))
      (node (ref "IC3") (pin "11") (pinfunction "D_11") (pintype "input"))
      (node (ref "IC3") (pin "8") (pinfunction "VSS_8") (pintype "power_in"))
      (node (ref "IC5") (pin "1") (pinfunction "GND_1") (pintype "power_in"))
      (node (ref "IC6") (pin "8") (pinfunction "GND_8") (pintype "power_in"))
      (node (ref "IC7") (pin "10") (pinfunction "-IN_10") (pintype "input"))
      (node (ref "IC7") (pin "11") (pinfunction "+IN_11") (pintype "input"))
      (node (ref "IC7") (pin "12") (pinfunction "GND_12") (pintype "power_in"))
      (node (ref "IC8") (pin "1") (pinfunction "T1_1") (pintype "input"))
      (node (ref "IC8") (pin "15") (pinfunction "T1_15") (pintype "input"))
      (node (ref "IC8") (pin "4") (pinfunction "A_4") (pintype "input"))
      (node (ref "IC8") (pin "8") (pinfunction "VSS_8") (pintype "power_in"))
      (node (ref "IC9") (pin "2") (pinfunction "GND_2") (pintype "input"))
      (node (ref "IC9") (pin "2@1") (pinfunction "GND_2@1") (pintype "input"))
      (node (ref "Q10") (pin "2") (pinfunction "S_2") (pintype "passive"))
      (node (ref "Q11") (pin "2") (pinfunction "S_2") (pintype "passive"))
      (node (ref "Q9") (pin "3") (pinfunction "E_3") (pintype "passive"))
      (node (ref "R14") (pin "2") (pinfunction "2_2") (pintype "passive"))
      (node (ref "R16") (pin "1") (pinfunction "1_1") (pintype "passive"))
      (node (ref "R2") (pin "1") (pinfunction "1_1") (pintype "passive"))
      (node (ref "R24") (pin "2") (pinfunction "2_2") (pintype "passive"))
      (node (ref "R36") (pin "1") (pinfunction "1_1") (pintype "passive"))
      (node (ref "R37") (pin "1") (pinfunction "1_1") (pintype "passive"))
      (node (ref "R38") (pin "2") (pinfunction "2_2") (pintype "passive"))
      (node (ref "R39") (pin "2") (pinfunction "2_2") (pintype "passive"))
      (node (ref "R4") (pin "2") (pinfunction "2_2") (pintype "passive"))
      (node (ref "R46") (pin "1") (pinfunction "1_1") (pintype "passive"))
      (node (ref "R8") (pin "1") (pinfunction "1_1") (pintype "passive"))
      (node (ref "T3") (pin "E") (pinfunction "E_E") (pintype "passive"))
      (node (ref "X1") (pin "13") (pinfunction "13_13") (pintype "passive"))
      (node (ref "X1") (pin "18") (pinfunction "18_18") (pintype "passive"))
      (node (ref "X1") (pin "23") (pinfunction "23_23") (pintype "passive"))
      (node (ref "X2") (pin "1") (pinfunction "S_1") (pintype "passive"))
      (node (ref "X3") (pin "5") (pinfunction "S_5") (pintype "passive"))
    )
    (net (code "4") (name "Net-(1A-KL)") (class "Default")
      (node (ref "1") (pin "1") (pinfunction "KL_1") (pintype "passive"))
      (node (ref "TP1") (pin "TP") (pinfunction "PP_TP") (pintype "input"))
      (node (ref "X1") (pin "1") (pinfunction "1_1") (pintype "passive"))
    )
    (net (code "5") (name "Net-(1B-KL)") (class "Default")
      (node (ref "1") (pin "10") (pinfunction "KL_10") (pintype "passive"))
      (node (ref "D10") (pin "2") (pinfunction "-_2") (pintype "passive"))
      (node (ref "D11") (pin "2") (pinfunction "-_2") (pintype "passive"))
      (node (ref "JP1") (pin "1") (pinfunction "1_1") (pintype "passive"))
      (node (ref "TP10") (pin "TP") (pinfunction "PP_TP") (pintype "input"))
    )
    (net (code "6") (name "Net-(1C-KL)") (class "Default")
      (node (ref "1") (pin "11") (pinfunction "KL_11") (pintype "passive"))
      (node (ref "D11") (pin "1") (pinfunction "+_1") (pintype "passive"))
      (node (ref "TP11") (pin "TP") (pinfunction "PP_TP") (pintype "input"))
      (node (ref "X1") (pin "19") (pinfunction "19_19") (pintype "passive"))
    )
    (net (code "7") (name "Net-(1E-KL)") (class "Default")
      (node (ref "1") (pin "2") (pinfunction "KL_2") (pintype "passive"))
      (node (ref "Q5") (pin "2") (pinfunction "C_2") (pintype "passive"))
      (node (ref "Q8") (pin "2") (pinfunction "C_2") (pintype "passive"))
      (node (ref "T1") (pin "8") (pinfunction "C1_8") (pintype "passive"))
      (node (ref "TP2") (pin "TP") (pinfunction "PP_TP") (pintype "input"))
    )
    (net (code "8") (name "Net-(1F-KL)") (class "Default")
      (node (ref "1") (pin "3") (pinfunction "KL_3") (pintype "passive"))
      (node (ref "IC6") (pin "11") (pinfunction "O6_11") (pintype "open_collector"))
      (node (ref "TP3") (pin "TP") (pinfunction "PP_TP") (pintype "input"))
    )
    (net (code "9") (name "Net-(1G-KL)") (class "Default")
      (node (ref "1") (pin "4") (pinfunction "KL_4") (pintype "passive"))
      (node (ref "IC6") (pin "10") (pinfunction "O7_10") (pintype "open_collector"))
      (node (ref "TP4") (pin "TP") (pinfunction "PP_TP") (pintype "input"))
    )
    (net (code "10") (name "Net-(1H-KL)") (class "Default")
      (node (ref "1") (pin "5") (pinfunction "KL_5") (pintype "passive"))
      (node (ref "IC6") (pin "12") (pinfunction "O5_12") (pintype "open_collector"))
      (node (ref "TP5") (pin "TP") (pinfunction "PP_TP") (pintype "input"))
    )
    (net (code "11") (name "Net-(1I-KL)") (class "Default")
      (node (ref "1") (pin "6") (pinfunction "KL_6") (pintype "passive"))
      (node (ref "IC6") (pin "13") (pinfunction "O4_13") (pintype "open_collector"))
      (node (ref "TP6") (pin "TP") (pinfunction "PP_TP") (pintype "input"))
    )
    (net (code "12") (name "Net-(1J-KL)") (class "Default")
      (node (ref "1") (pin "7") (pinfunction "KL_7") (pintype "passive"))
      (node (ref "IC6") (pin "14") (pinfunction "O3_14") (pintype "open_collector"))
      (node (ref "TP7") (pin "TP") (pinfunction "PP_TP") (pintype "input"))
    )
    (net (code "13") (name "Net-(1K-KL)") (class "Default")
      (node (ref "1") (pin "8") (pinfunction "KL_8") (pintype "passive"))
      (node (ref "Q11") (pin "3") (pinfunction "D_3") (pintype "passive"))
      (node (ref "TP8") (pin "TP") (pinfunction "PP_TP") (pintype "input"))
    )
    (net (code "14") (name "Net-(1L-KL)") (class "Default")
      (node (ref "1") (pin "9") (pinfunction "KL_9") (pintype "passive"))
      (node (ref "D10") (pin "1") (pinfunction "+_1") (pintype "passive"))
      (node (ref "TP9") (pin "TP") (pinfunction "PP_TP") (pintype "input"))
      (node (ref "X1") (pin "17") (pinfunction "17_17") (pintype "passive"))
    )
    (net (code "15") (name "Net-(2B-KL)") (class "Default")
      (node (ref "2") (pin "10") (pinfunction "KL_10") (pintype "passive"))
      (node (ref "TP25") (pin "TP") (pinfunction "PP_TP") (pintype "input"))
      (node (ref "X1") (pin "15") (pinfunction "15_15") (pintype "passive"))
    )
    (net (code "16") (name "Net-(2C-KL)") (class "Default")
      (node (ref "2") (pin "11") (pinfunction "KL_11") (pintype "passive"))
      (node (ref "R23") (pin "1") (pinfunction "1_1") (pintype "passive"))
      (node (ref "R3") (pin "1") (pinfunction "1_1") (pintype "passive"))
      (node (ref "TP26") (pin "TP") (pinfunction "PP_TP") (pintype "input"))
    )
    (net (code "17") (name "Net-(2D-KL)") (class "Default")
      (node (ref "2") (pin "12") (pinfunction "KL_12") (pintype "passive"))
      (node (ref "R35") (pin "1") (pinfunction "1_1") (pintype "passive"))
      (node (ref "TP13") (pin "TP") (pinfunction "PP_TP") (pintype "input"))
    )
    (net (code "18") (name "Net-(2E-KL)") (class "Default")
      (node (ref "2") (pin "2") (pinfunction "KL_2") (pintype "passive"))
      (node (ref "D13") (pin "2") (pinfunction "-_2") (pintype "passive"))
      (node (ref "LED1") (pin "K") (pinfunction "C_K") (pintype "passive"))
      (node (ref "TP16") (pin "TP") (pinfunction "PP_TP") (pintype "input"))
      (node (ref "X1") (pin "12") (pinfunction "12_12") (pintype "passive"))
    )
    (net (code "19") (name "Net-(2F-KL)") (class "Default")
      (node (ref "2") (pin "3") (pinfunction "KL_3") (pintype "passive"))
      (node (ref "D12") (pin "2") (pinfunction "-_2") (pintype "passive"))
      (node (ref "LED2") (pin "K") (pinfunction "C_K") (pintype "passive"))
      (node (ref "TP17") (pin "TP") (pinfunction "PP_TP") (pintype "input"))
      (node (ref "X1") (pin "11") (pinfunction "11_11") (pintype "passive"))
    )
    (net (code "20") (name "Net-(2G-KL)") (class "Default")
      (node (ref "2") (pin "4") (pinfunction "KL_4") (pintype "passive"))
      (node (ref "D2") (pin "2") (pinfunction "-_2") (pintype "passive"))
      (node (ref "LED3") (pin "K") (pinfunction "C_K") (pintype "passive"))
      (node (ref "TP18") (pin "TP") (pinfunction "PP_TP") (pintype "input"))
      (node (ref "X1") (pin "10") (pinfunction "10_10") (pintype "passive"))
    )
    (net (code "21") (name "Net-(2H-KL)") (class "Default")
      (node (ref "2") (pin "5") (pinfunction "KL_5") (pintype "passive"))
      (node (ref "D1") (pin "2") (pinfunction "-_2") (pintype "passive"))
      (node (ref "LED4") (pin "K") (pinfunction "C_K") (pintype "passive"))
      (node (ref "TP19") (pin "TP") (pinfunction "PP_TP") (pintype "input"))
      (node (ref "X1") (pin "9") (pinfunction "9_9") (pintype "passive"))
    )
    (net (code "22") (name "Net-(2I-KL)") (class "Default")
      (node (ref "2") (pin "6") (pinfunction "KL_6") (pintype "passive"))
      (node (ref "R14") (pin "1") (pinfunction "1_1") (pintype "passive"))
      (node (ref "R7") (pin "1") (pinfunction "1_1") (pintype "passive"))
      (node (ref "TP21") (pin "TP") (pinfunction "PP_TP") (pintype "input"))
    )
    (net (code "23") (name "Net-(2J-KL)") (class "Default")
      (node (ref "2") (pin "7") (pinfunction "KL_7") (pintype "passive"))
      (node (ref "LED6") (pin "A") (pinfunction "A_A") (pintype "passive"))
      (node (ref "TP22") (pin "TP") (pinfunction "PP_TP") (pintype "input"))
      (node (ref "X1") (pin "8") (pinfunction "8_8") (pintype "passive"))
    )
    (net (code "24") (name "Net-(2K-KL)") (class "Default")
      (node (ref "2") (pin "8") (pinfunction "KL_8") (pintype "passive"))
      (node (ref "D14") (pin "2") (pinfunction "-_2") (pintype "passive"))
      (node (ref "LED7") (pin "K") (pinfunction "C_K") (pintype "passive"))
      (node (ref "TP23") (pin "TP") (pinfunction "PP_TP") (pintype "input"))
      (node (ref "X1") (pin "14") (pinfunction "14_14") (pintype "passive"))
    )
    (net (code "25") (name "Net-(2L-KL)") (class "Default")
      (node (ref "2") (pin "9") (pinfunction "KL_9") (pintype "passive"))
      (node (ref "D12") (pin "1") (pinfunction "+_1") (pintype "passive"))
      (node (ref "D2") (pin "1") (pinfunction "+_1") (pintype "passive"))
      (node (ref "JP5") (pin "2") (pinfunction "2_2") (pintype "passive"))
      (node (ref "JP6") (pin "2") (pinfunction "2_2") (pintype "passive"))
      (node (ref "TP24") (pin "TP") (pinfunction "PP_TP") (pintype "input"))
    )
    (net (code "26") (name "Net-(C2-Pad1)") (class "Default")
      (node (ref "C2") (pin "1") (pinfunction "1_1") (pintype "passive"))
      (node (ref "R10") (pin "1") (pinfunction "1_1") (pintype "passive"))
      (node (ref "R12") (pin "2") (pinfunction "2_2") (pintype "passive"))
    )
    (net (code "27") (name "Net-(C11-Pad1)") (class "Default")
      (node (ref "C11") (pin "1") (pinfunction "1_1") (pintype "passive"))
      (node (ref "R42") (pin "1") (pinfunction "1_1") (pintype "passive"))
      (node (ref "R43") (pin "1") (pinfunction "1_1") (pintype "passive"))
    )
    (net (code "28") (name "Net-(D1-+)") (class "Default")
      (node (ref "D1") (pin "1") (pinfunction "+_1") (pintype "passive"))
      (node (ref "R27") (pin "1") (pinfunction "1_1") (pintype "passive"))
    )
    (net (code "29") (name "Net-(D3-+)") (class "Default")
      (node (ref "D3") (pin "1") (pinfunction "+_1") (pintype "passive"))
      (node (ref "R33") (pin "1") (pinfunction "1_1") (pintype "passive"))
    )
    (net (code "30") (name "Net-(D3--)") (class "Default")
      (node (ref "C1") (pin "2") (pinfunction "2_2") (pintype "passive"))
      (node (ref "D3") (pin "2") (pinfunction "-_2") (pintype "passive"))
      (node (ref "IC5") (pin "2") (pinfunction "TR_2") (pintype "input"))
      (node (ref "IC5") (pin "6") (pinfunction "THR_6") (pintype "input"))
      (node (ref "R24") (pin "1") (pinfunction "1_1") (pintype "passive"))
    )
    (net (code "31") (name "Net-(D8-+)") (class "Default")
      (node (ref "D8") (pin "1") (pinfunction "+_1") (pintype "passive"))
      (node (ref "R17") (pin "1") (pinfunction "1_1") (pintype "passive"))
    )
    (net (code "32") (name "Net-(D8--)") (class "Default")
      (node (ref "D8") (pin "2") (pinfunction "-_2") (pintype "passive"))
      (node (ref "IC7") (pin "2") (pinfunction "OUT_2") (pintype "open_collector"))
      (node (ref "Q10") (pin "1") (pinfunction "G_1") (pintype "passive"))
      (node (ref "R22") (pin "2") (pinfunction "2_2") (pintype "passive"))
    )
    (net (code "33") (name "Net-(D13-+)") (class "Default")
      (node (ref "D13") (pin "1") (pinfunction "+_1") (pintype "passive"))
      (node (ref "JP5") (pin "1") (pinfunction "1_1") (pintype "passive"))
    )
    (net (code "34") (name "Net-(D14-+)") (class "Default")
      (node (ref "D14") (pin "1") (pinfunction "+_1") (pintype "passive"))
      (node (ref "JP6") (pin "1") (pinfunction "1_1") (pintype "passive"))
    )
    (net (code "35") (name "Net-(D15--)") (class "Default")
      (node (ref "D15") (pin "2") (pinfunction "-_2") (pintype "passive"))
      (node (ref "Q1") (pin "2") (pinfunction "C_2") (pintype "passive"))
      (node (ref "Q3") (pin "2") (pinfunction "C_2") (pintype "passive"))
      (node (ref "START") (pin "TP") (pinfunction "PP_TP") (pintype "input"))
      (node (ref "X1") (pin "5") (pinfunction "5_5") (pintype "passive"))
    )
    (net (code "36") (name "Net-(IC3A-A)") (class "Default")
      (node (ref "IC3") (pin "10") (pinfunction "A_10") (pintype "input"))
      (node (ref "R31") (pin "1") (pinfunction "1_1") (pintype "passive"))
      (node (ref "X1") (pin "4") (pinfunction "4_4") (pintype "passive"))
      (node (ref "X3") (pin "2") (pinfunction "S_2") (pintype "passive"))
    )
    (net (code "37") (name "Net-(IC3A-B)") (class "Default")
      (node (ref "IC3") (pin "13") (pinfunction "B_13") (pintype "input"))
      (node (ref "R30") (pin "1") (pinfunction "1_1") (pintype "passive"))
      (node (ref "X1") (pin "3") (pinfunction "3_3") (pintype "passive"))
      (node (ref "X3") (pin "3") (pinfunction "S_3") (pintype "passive"))
    )
    (net (code "38") (name "Net-(IC3A-C)") (class "Default")
      (node (ref "IC3") (pin "12") (pinfunction "C_12") (pintype "input"))
      (node (ref "R29") (pin "1") (pinfunction "1_1") (pintype "passive"))
      (node (ref "X1") (pin "2") (pinfunction "2_2") (pintype "passive"))
      (node (ref "X3") (pin "4") (pinfunction "S_4") (pintype "passive"))
    )
    (net (code "39") (name "Net-(IC3A-Q0)") (class "Default")
      (node (ref "IC3") (pin "3") (pinfunction "Q0_3") (pintype "output"))
      (node (ref "IC6") (pin "1") (pinfunction "I1_1") (pintype "input"))
      (node (ref "IC6") (pin "2") (pinfunction "I2_2") (pintype "input"))
      (node (ref "Q11") (pin "1") (pinfunction "G_1") (pintype "passive"))
    )
    (net (code "40") (name "Net-(IC3A-Q1)") (class "Default")
      (node (ref "IC3") (pin "14") (pinfunction "Q1_14") (pintype "output"))
      (node (ref "IC6") (pin "6") (pinfunction "I6_6") (pintype "input"))
    )
    (net (code "41") (name "Net-(IC3A-Q2)") (class "Default")
      (node (ref "IC3") (pin "2") (pinfunction "Q2_2") (pintype "output"))
      (node (ref "IC6") (pin "7") (pinfunction "I7_7") (pintype "input"))
    )
    (net (code "42") (name "Net-(IC3A-Q3)") (class "Default")
      (node (ref "IC3") (pin "15") (pinfunction "Q3_15") (pintype "output"))
      (node (ref "IC6") (pin "5") (pinfunction "I5_5") (pintype "input"))
    )
    (net (code "43") (name "Net-(IC3A-Q4)") (class "Default")
      (node (ref "IC3") (pin "1") (pinfunction "Q4_1") (pintype "output"))
      (node (ref "IC6") (pin "4") (pinfunction "I4_4") (pintype "input"))
    )
    (net (code "44") (name "Net-(IC3A-Q5)") (class "Default")
      (node (ref "IC3") (pin "6") (pinfunction "Q5_6") (pintype "output"))
      (node (ref "IC6") (pin "3") (pinfunction "I3_3") (pintype "input"))
    )
    (net (code "45") (name "Net-(IC4-ADJ)") (class "Default")
      (node (ref "IC4") (pin "1") (pinfunction "ADJ_1") (pintype "input"))
      (node (ref "R18") (pin "1") (pinfunction "1_1") (pintype "passive"))
      (node (ref "R5") (pin "2") (pinfunction "2_2") (pintype "passive"))
      (node (ref "X1") (pin "7") (pinfunction "7_7") (pintype "passive"))
    )
    (net (code "46") (name "Net-(IC4-VI)") (class "Default")
      (node (ref "IC4") (pin "3") (pinfunction "VI_3") (pintype "input"))
      (node (ref "Q2") (pin "2") (pinfunction "C_2") (pintype "passive"))
      (node (ref "Q4") (pin "2") (pinfunction "C_2") (pintype "passive"))
    )
    (net (code "47") (name "Net-(IC4-VO)") (class "Default")
      (node (ref "IC4") (pin "2") (pinfunction "VO_2") (pintype "passive"))
      (node (ref "R18") (pin "2") (pinfunction "2_2") (pintype "passive"))
    )
    (net (code "48") (name "Net-(IC5-CV)") (class "Default")
      (node (ref "IC5") (pin "5") (pinfunction "CV_5") (pintype "input"))
      (node (ref "R26") (pin "2") (pinfunction "2_2") (pintype "passive"))
    )
    (net (code "49") (name "Net-(IC5-Q)") (class "Default")
      (node (ref "IC5") (pin "3") (pinfunction "Q_3") (pintype "output"))
      (node (ref "IC8") (pin "12") (pinfunction "A_12") (pintype "input"))
      (node (ref "R26") (pin "1") (pinfunction "1_1") (pintype "passive"))
    )
    (net (code "50") (name "Net-(IC6-O1)") (class "Default")
      (node (ref "IC6") (pin "16") (pinfunction "O1_16") (pintype "open_collector"))
      (node (ref "Q9") (pin "2") (pinfunction "C_2") (pintype "passive"))
      (node (ref "R3") (pin "2") (pinfunction "2_2") (pintype "passive"))
      (node (ref "T3") (pin "C") (pinfunction "C_C") (pintype "passive"))
      (node (ref "X1") (pin "21") (pinfunction "21_21") (pintype "passive"))
    )
    (net (code "51") (name "Net-(IC6-O2)") (class "Default")
      (node (ref "IC6") (pin "15") (pinfunction "O2_15") (pintype "open_collector"))
      (node (ref "R13") (pin "1") (pinfunction "1_1") (pintype "passive"))
    )
    (net (code "52") (name "Net-(IC7A-+IN)") (class "Default")
      (node (ref "IC7") (pin "5") (pinfunction "+IN_5") (pintype "input"))
      (node (ref "R15") (pin "1") (pinfunction "1_1") (pintype "passive"))
      (node (ref "R16") (pin "2") (pinfunction "2_2") (pintype "passive"))
      (node (ref "R17") (pin "2") (pinfunction "2_2") (pintype "passive"))
    )
    (net (code "53") (name "Net-(IC7A--IN)") (class "Default")
      (node (ref "C3") (pin "1") (pinfunction "1_1") (pintype "passive"))
      (node (ref "IC7") (pin "4") (pinfunction "-IN_4") (pintype "input"))
      (node (ref "R12") (pin "1") (pinfunction "1_1") (pintype "passive"))
    )
    (net (code "54") (name "Net-(IC7B-+IN)") (class "Default")
      (node (ref "IC7") (pin "7") (pinfunction "+IN_7") (pintype "input"))
      (node (ref "R25") (pin "1") (pinfunction "1_1") (pintype "passive"))
      (node (ref "R6") (pin "1") (pinfunction "1_1") (pintype "passive"))
    )
    (net (code "55") (name "Net-(IC7B--IN)") (class "Default")
      (node (ref "IC7") (pin "6") (pinfunction "-IN_6") (pintype "input"))
      (node (ref "IC7") (pin "8") (pinfunction "-IN_8") (pintype "input"))
      (node (ref "R5") (pin "1") (pinfunction "1_1") (pintype "passive"))
    )
    (net (code "56") (name "Net-(IC7B-OUT)") (class "Default")
      (node (ref "IC7") (pin "1") (pinfunction "OUT_1") (pintype "open_collector"))
      (node (ref "R10") (pin "2") (pinfunction "2_2") (pintype "passive"))
      (node (ref "R19") (pin "2") (pinfunction "2_2") (pintype "passive"))
    )
    (net (code "57") (name "Net-(IC7C-+IN)") (class "Default")
      (node (ref "C5") (pin "1") (pinfunction "1_1") (pintype "passive"))
      (node (ref "IC7") (pin "9") (pinfunction "+IN_9") (pintype "input"))
      (node (ref "R25") (pin "2") (pinfunction "2_2") (pintype "passive"))
      (node (ref "R8") (pin "2") (pinfunction "2_2") (pintype "passive"))
    )
    (net (code "58") (name "Net-(IC7C-OUT)") (class "Default")
      (node (ref "C9") (pin "2") (pinfunction "2_2") (pintype "passive"))
      (node (ref "IC7") (pin "14") (pinfunction "OUT_14") (pintype "open_collector"))
      (node (ref "R9") (pin "2") (pinfunction "2_2") (pintype "passive"))
    )
    (net (code "59") (name "Net-(IC8B-B)") (class "Default")
      (node (ref "IC8") (pin "11") (pinfunction "B_11") (pintype "input"))
      (node (ref "IC8") (pin "9") (pinfunction "~{Q}_9") (pintype "output"))
      (node (ref "R35") (pin "2") (pinfunction "2_2") (pintype "passive"))
    )
    (net (code "60") (name "Net-(IC8B-T2)") (class "Default")
      (node (ref "C10") (pin "1") (pinfunction "1_1") (pintype "passive"))
      (node (ref "IC8") (pin "14") (pinfunction "T2_14") (pintype "input"))
      (node (ref "R34") (pin "1") (pinfunction "1_1") (pintype "passive"))
    )
    (net (code "61") (name "Net-(IC10A-+IN)") (class "Default")
      (node (ref "C8") (pin "1") (pinfunction "1_1") (pintype "passive"))
      (node (ref "IC10") (pin "3") (pinfunction "+IN_3") (pintype "input"))
      (node (ref "R1") (pin "1") (pinfunction "1_1") (pintype "passive"))
    )
    (net (code "62") (name "Net-(IC10A--IN)") (class "Default")
      (node (ref "IC10") (pin "2") (pinfunction "-IN_2") (pintype "input"))
      (node (ref "R2") (pin "2") (pinfunction "2_2") (pintype "passive"))
    )
    (net (code "63") (name "Net-(IC10A-OUT)") (class "Default")
      (node (ref "IC10") (pin "1") (pinfunction "OUT_1") (pintype "output"))
      (node (ref "R42") (pin "2") (pinfunction "2_2") (pintype "passive"))
    )
    (net (code "64") (name "Net-(IC10B-+IN)") (class "Default")
      (node (ref "IC10") (pin "5") (pinfunction "+IN_5") (pintype "input"))
      (node (ref "R43") (pin "2") (pinfunction "2_2") (pintype "passive"))
      (node (ref "R44") (pin "2") (pinfunction "2_2") (pintype "passive"))
    )
    (net (code "65") (name "Net-(IC10B--IN)") (class "Default")
      (node (ref "IC10") (pin "6") (pinfunction "-IN_6") (pintype "input"))
      (node (ref "R45") (pin "1") (pinfunction "1_1") (pintype "passive"))
      (node (ref "R46") (pin "2") (pinfunction "2_2") (pintype "passive"))
    )
    (net (code "66") (name "Net-(IC10B-OUT)") (class "Default")
      (node (ref "IC10") (pin "7") (pinfunction "OUT_7") (pintype "output"))
      (node (ref "R32") (pin "1") (pinfunction "1_1") (pintype "passive"))
      (node (ref "R44") (pin "1") (pinfunction "1_1") (pintype "passive"))
    )
    (net (code "67") (name "Net-(JP1-Pad2)") (class "Default")
      (node (ref "JP1") (pin "2") (pinfunction "2_2") (pintype "passive"))
      (node (ref "R36") (pin "2") (pinfunction "2_2") (pintype "passive"))
      (node (ref "R37") (pin "2") (pinfunction "2_2") (pintype "passive"))
    )
    (net (code "68") (name "Net-(JP3-Pad1)") (class "Default")
      (node (ref "JP3") (pin "1") (pinfunction "1_1") (pintype "passive"))
      (node (ref "R23") (pin "2") (pinfunction "2_2") (pintype "passive"))
    )
    (net (code "69") (name "Net-(LED1-PadA)") (class "Default")
      (node (ref "LED1") (pin "A") (pinfunction "A_A") (pintype "passive"))
      (node (ref "LED2") (pin "A") (pinfunction "A_A") (pintype "passive"))
      (node (ref "LED3") (pin "A") (pinfunction "A_A") (pintype "passive"))
      (node (ref "LED4") (pin "A") (pinfunction "A_A") (pintype "passive"))
      (node (ref "LED7") (pin "A") (pinfunction "A_A") (pintype "passive"))
      (node (ref "R11") (pin "1") (pinfunction "1_1") (pintype "passive"))
    )
    (net (code "70") (name "Net-(LED6-C)") (class "Default")
      (node (ref "LED6") (pin "K") (pinfunction "C_K") (pintype "passive"))
      (node (ref "R4") (pin "1") (pinfunction "1_1") (pintype "passive"))
    )
    (net (code "71") (name "Net-(Q1-B)") (class "Default")
      (node (ref "Q1") (pin "1") (pinfunction "B_1") (pintype "passive"))
      (node (ref "Q3") (pin "1") (pinfunction "B_1") (pintype "passive"))
      (node (ref "R13") (pin "2") (pinfunction "2_2") (pintype "passive"))
    )
    (net (code "72") (name "Net-(Q2-B)") (class "Default")
      (node (ref "Q2") (pin "1") (pinfunction "B_1") (pintype "passive"))
      (node (ref "Q4") (pin "1") (pinfunction "B_1") (pintype "passive"))
      (node (ref "R9") (pin "1") (pinfunction "1_1") (pintype "passive"))
    )
    (net (code "73") (name "Net-(Q5-B)") (class "Default")
      (node (ref "Q5") (pin "1") (pinfunction "B_1") (pintype "passive"))
      (node (ref "Q6") (pin "1") (pinfunction "B_1") (pintype "passive"))
      (node (ref "Q6") (pin "2") (pinfunction "C_2") (pintype "passive"))
      (node (ref "Q7") (pin "1") (pinfunction "B_1") (pintype "passive"))
      (node (ref "Q7") (pin "2") (pinfunction "C_2") (pintype "passive"))
      (node (ref "Q8") (pin "1") (pinfunction "B_1") (pintype "passive"))
      (node (ref "R38") (pin "1") (pinfunction "1_1") (pintype "passive"))
      (node (ref "R39") (pin "1") (pinfunction "1_1") (pintype "passive"))
      (node (ref "T1") (pin "2") (pinfunction "B_2") (pintype "passive"))
      (node (ref "T1") (pin "4") (pinfunction "B_4") (pintype "passive"))
      (node (ref "T1") (pin "6") (pinfunction "C1_6") (pintype "passive"))
      (node (ref "X2") (pin "2") (pinfunction "S_2") (pintype "passive"))
    )
    (net (code "74") (name "Net-(Q5-E)") (class "Default")
      (node (ref "Q5") (pin "3") (pinfunction "E_3") (pintype "passive"))
      (node (ref "Q8") (pin "3") (pinfunction "E_3") (pintype "passive"))
      (node (ref "R21") (pin "2") (pinfunction "2_2") (pintype "passive"))
      (node (ref "T1") (pin "1") (pinfunction "E_1") (pintype "passive"))
    )
    (net (code "75") (name "Net-(Q6-E)") (class "Default")
      (node (ref "Q6") (pin "3") (pinfunction "E_3") (pintype "passive"))
      (node (ref "Q7") (pin "3") (pinfunction "E_3") (pintype "passive"))
      (node (ref "R20") (pin "2") (pinfunction "2_2") (pintype "passive"))
      (node (ref "T1") (pin "3") (pinfunction "E_3") (pintype "passive"))
    )
    (net (code "76") (name "Net-(Q9-B)") (class "Default")
      (node (ref "Q9") (pin "1") (pinfunction "B_1") (pintype "passive"))
      (node (ref "R32") (pin "2") (pinfunction "2_2") (pintype "passive"))
      (node (ref "T3") (pin "B") (pinfunction "B_B") (pintype "passive"))
    )
    (net (code "77") (name "Net-(Q10-D)") (class "Default")
      (node (ref "Q10") (pin "3") (pinfunction "D_3") (pintype "passive"))
      (node (ref "R7") (pin "2") (pinfunction "2_2") (pintype "passive"))
    )
    (net (code "78") (name "Net-(R1-Pad2)") (class "Default")
      (node (ref "R1") (pin "2") (pinfunction "2_2") (pintype "passive"))
      (node (ref "X1") (pin "22") (pinfunction "22_22") (pintype "passive"))
    )
    (net (code "79") (name "Net-(R27-Pad2)") (class "Default")
      (node (ref "R27") (pin "2") (pinfunction "2_2") (pintype "passive"))
      (node (ref "R28") (pin "1") (pinfunction "1_1") (pintype "passive"))
    )
    (net (code "80") (name "Net-(R33-Pad2)") (class "Default")
      (node (ref "R33") (pin "2") (pinfunction "2_2") (pintype "passive"))
      (node (ref "X1") (pin "16") (pinfunction "16_16") (pintype "passive"))
    )
    (net (code "81") (name "Net-(TACHO_BEL-PP)") (class "Default")
      (node (ref "TACHO_BEL") (pin "TP") (pinfunction "PP_TP") (pintype "input"))
      (node (ref "X1") (pin "24") (pinfunction "24_24") (pintype "passive"))
    )
    (net (code "82") (name "VCC") (class "Default")
      (node (ref "6V") (pin "TP") (pinfunction "PP_TP") (pintype "input"))
      (node (ref "C4") (pin "1") (pinfunction "1_1") (pintype "passive"))
      (node (ref "IC1") (pin "OUT") (pinfunction "OUT_OUT") (pintype "passive"))
      (node (ref "IC10") (pin "8") (pinfunction "V+_8") (pintype "power_in"))
      (node (ref "IC2") (pin "1") (pinfunction "OUT_1") (pintype "passive"))
      (node (ref "IC7") (pin "3") (pinfunction "V+_3") (pintype "power_in"))
      (node (ref "R11") (pin "2") (pinfunction "2_2") (pintype "passive"))
      (node (ref "R15") (pin "2") (pinfunction "2_2") (pintype "passive"))
      (node (ref "R19") (pin "1") (pinfunction "1_1") (pintype "passive"))
      (node (ref "R45") (pin "2") (pinfunction "2_2") (pintype "passive"))
      (node (ref "R6") (pin "2") (pinfunction "2_2") (pintype "passive"))
    )
    (net (code "83") (name "unconnected-(IC3A-Q6-Pad7)") (class "Default")
      (node (ref "IC3") (pin "7") (pinfunction "Q6_7") (pintype "output"))
    )
    (net (code "84") (name "unconnected-(IC3A-Q7-Pad4)") (class "Default")
      (node (ref "IC3") (pin "4") (pinfunction "Q7_4") (pintype "output"))
    )
    (net (code "85") (name "unconnected-(IC3A-Q8-Pad9)") (class "Default")
      (node (ref "IC3") (pin "9") (pinfunction "Q8_9") (pintype "output"))
    )
    (net (code "86") (name "unconnected-(IC3A-Q9-Pad5)") (class "Default")
      (node (ref "IC3") (pin "5") (pinfunction "Q9_5") (pintype "output"))
    )
    (net (code "87") (name "unconnected-(IC5-DIS-Pad7)") (class "Default")
      (node (ref "IC5") (pin "7") (pinfunction "DIS_7") (pintype "input"))
    )
    (net (code "88") (name "unconnected-(IC6-CD+-Pad9)") (class "Default")
      (node (ref "IC6") (pin "9") (pinfunction "CD+_9") (pintype "passive"))
    )
    (net (code "89") (name "unconnected-(IC7D-OUT-Pad13)") (class "Default")
      (node (ref "IC7") (pin "13") (pinfunction "OUT_13") (pintype "open_collector"))
    )
    (net (code "90") (name "unconnected-(IC8A-Q-Pad6)") (class "Default")
      (node (ref "IC8") (pin "6") (pinfunction "Q_6") (pintype "output"))
    )
    (net (code "91") (name "unconnected-(IC8A-T2-Pad2)") (class "Default")
      (node (ref "IC8") (pin "2") (pinfunction "T2_2") (pintype "input"))
    )
    (net (code "92") (name "unconnected-(IC8A-~{Q}-Pad7)") (class "Default")
      (node (ref "IC8") (pin "7") (pinfunction "~{Q}_7") (pintype "output"))
    )
    (net (code "93") (name "unconnected-(IC8B-Q-Pad10)") (class "Default")
      (node (ref "IC8") (pin "10") (pinfunction "Q_10") (pintype "output"))
    )
    (net (code "94") (name "unconnected-(Q3-C{slash}-Pad4)") (class "Default")
      (node (ref "Q3") (pin "4") (pinfunction "C/_4") (pintype "passive"))
    )
    (net (code "95") (name "unconnected-(Q4-C{slash}-Pad4)") (class "Default")
      (node (ref "Q4") (pin "4") (pinfunction "C/_4") (pintype "passive"))
    )
    (net (code "96") (name "unconnected-(Q5-C{slash}-Pad4)") (class "Default")
      (node (ref "Q5") (pin "4") (pinfunction "C/_4") (pintype "passive"))
    )
    (net (code "97") (name "unconnected-(Q6-C{slash}-Pad4)") (class "Default")
      (node (ref "Q6") (pin "4") (pinfunction "C/_4") (pintype "passive"))
    )
    (net (code "98") (name "unconnected-(T1A-C-Pad5)") (class "Default")
      (node (ref "T1") (pin "5") (pinfunction "C_5") (pintype "passive"))
    )
    (net (code "99") (name "unconnected-(T1B-C-Pad7)") (class "Default")
      (node (ref "T1") (pin "7") (pinfunction "C_7") (pintype "passive"))
    )
    (net (code "100") (name "unconnected-(X1-Pad20)") (class "Default")
      (node (ref "X1") (pin "20") (pinfunction "20_20") (pintype "passive"))
    )
  )
)
